# Distribution_Amp.net
KiCad netlist of a schematic drawn in Altium Designer
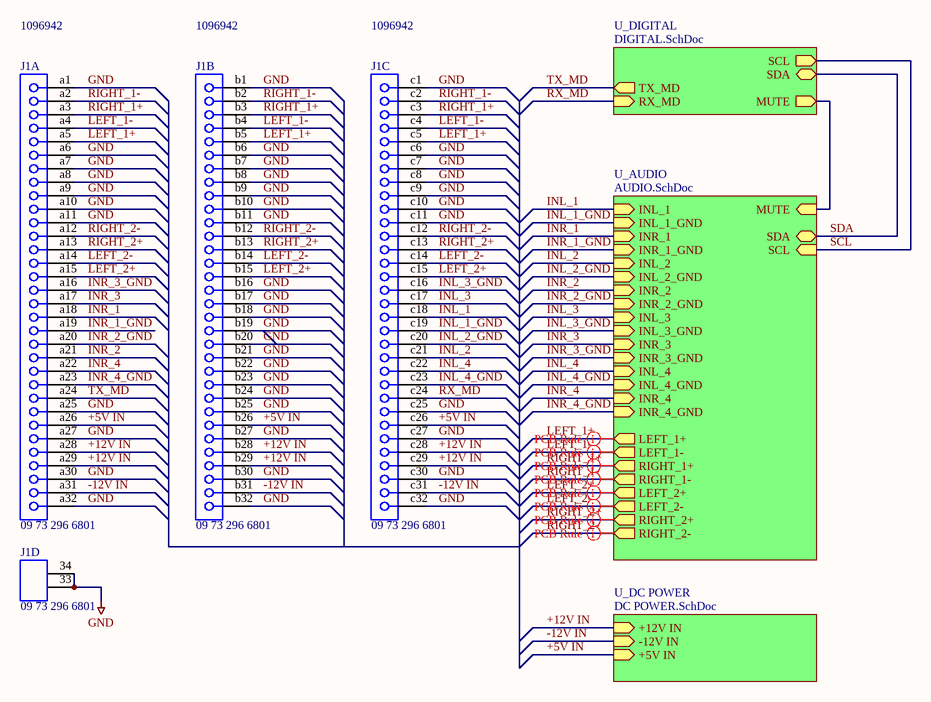
[diagram p0: Distribution Amp.SchDoc]

(export (version "E")
  (design (tool "Eeschema 10.0.6"))
  (components
    (comp (ref "J1")
      (value "09 73 296 6801")
      (footprint "0973296X801")
      (fields
        (field (name "MANUFACTURER") "HARTING")
        (field (name "MANUFACTURER PART NO.") "09732966801")
        (field (name "MOUSER PART NO.") "617-09-73-296-6801")
        (field (name "SUPPLIER PART NUMBER 3") "1096942")
      )
      (libsource (lib "HARTING DIN 41612 Type R") (part "09 73 296 6801"))
    )
  )
  (nets
    (net (code "1") (name "/+5V IN") (class "Default")
      (node (ref "J1") (pin "a26") (pinfunction "a26_a26") (pintype "passive"))
      (node (ref "J1") (pin "b26") (pinfunction "b26_b26") (pintype "passive"))
      (node (ref "J1") (pin "c26") (pinfunction "c26_c26") (pintype "passive"))
    )
    (net (code "2") (name "/+12V IN") (class "Default")
      (node (ref "J1") (pin "a28") (pinfunction "a28_a28") (pintype "passive"))
      (node (ref "J1") (pin "a29") (pinfunction "a29_a29") (pintype "passive"))
      (node (ref "J1") (pin "b28") (pinfunction "b28_b28") (pintype "passive"))
      (node (ref "J1") (pin "b29") (pinfunction "b29_b29") (pintype "passive"))
      (node (ref "J1") (pin "c28") (pinfunction "c28_c28") (pintype "passive"))
      (node (ref "J1") (pin "c29") (pinfunction "c29_c29") (pintype "passive"))
    )
    (net (code "3") (name "/-12V IN") (class "Default")
      (node (ref "J1") (pin "a31") (pinfunction "a31_a31") (pintype "passive"))
      (node (ref "J1") (pin "b31") (pinfunction "b31_b31") (pintype "passive"))
      (node (ref "J1") (pin "c31") (pinfunction "c31_c31") (pintype "passive"))
    )
    (net (code "4") (name "/INL_1") (class "Default")
      (node (ref "J1") (pin "c18") (pinfunction "c18_c18") (pintype "passive"))
    )
    (net (code "5") (name "/INL_1_GND") (class "Default")
      (node (ref "J1") (pin "c19") (pinfunction "c19_c19") (pintype "passive"))
    )
    (net (code "6") (name "/INL_2") (class "Default")
      (node (ref "J1") (pin "c21") (pinfunction "c21_c21") (pintype "passive"))
    )
    (net (code "7") (name "/INL_2_GND") (class "Default")
      (node (ref "J1") (pin "c20") (pinfunction "c20_c20") (pintype "passive"))
    )
    (net (code "8") (name "/INL_3") (class "Default")
      (node (ref "J1") (pin "c17") (pinfunction "c17_c17") (pintype "passive"))
    )
    (net (code "9") (name "/INL_3_GND") (class "Default")
      (node (ref "J1") (pin "c16") (pinfunction "c16_c16") (pintype "passive"))
    )
    (net (code "10") (name "/INL_4") (class "Default")
      (node (ref "J1") (pin "c22") (pinfunction "c22_c22") (pintype "passive"))
    )
    (net (code "11") (name "/INL_4_GND") (class "Default")
      (node (ref "J1") (pin "c23") (pinfunction "c23_c23") (pintype "passive"))
    )
    (net (code "12") (name "/INR_1") (class "Default")
      (node (ref "J1") (pin "a18") (pinfunction "a18_a18") (pintype "passive"))
    )
    (net (code "13") (name "/INR_1_GND") (class "Default")
      (node (ref "J1") (pin "a19") (pinfunction "a19_a19") (pintype "passive"))
    )
    (net (code "14") (name "/INR_2") (class "Default")
      (node (ref "J1") (pin "a21") (pinfunction "a21_a21") (pintype "passive"))
    )
    (net (code "15") (name "/INR_2_GND") (class "Default")
      (node (ref "J1") (pin "a20") (pinfunction "a20_a20") (pintype "passive"))
    )
    (net (code "16") (name "/INR_3") (class "Default")
      (node (ref "J1") (pin "a17") (pinfunction "a17_a17") (pintype "passive"))
    )
    (net (code "17") (name "/INR_3_GND") (class "Default")
      (node (ref "J1") (pin "a16") (pinfunction "a16_a16") (pintype "passive"))
    )
    (net (code "18") (name "/INR_4") (class "Default")
      (node (ref "J1") (pin "a22") (pinfunction "a22_a22") (pintype "passive"))
    )
    (net (code "19") (name "/INR_4_GND") (class "Default")
      (node (ref "J1") (pin "a23") (pinfunction "a23_a23") (pintype "passive"))
    )
    (net (code "20") (name "/LEFT_1+") (class "Default")
      (node (ref "J1") (pin "a5") (pinfunction "a5_a5") (pintype "passive"))
      (node (ref "J1") (pin "b5") (pinfunction "b5_b5") (pintype "passive"))
      (node (ref "J1") (pin "c5") (pinfunction "c5_c5") (pintype "passive"))
    )
    (net (code "21") (name "/LEFT_1-") (class "Default")
      (node (ref "J1") (pin "a4") (pinfunction "a4_a4") (pintype "passive"))
      (node (ref "J1") (pin "b4") (pinfunction "b4_b4") (pintype "passive"))
      (node (ref "J1") (pin "c4") (pinfunction "c4_c4") (pintype "passive"))
    )
    (net (code "22") (name "/LEFT_2+") (class "Default")
      (node (ref "J1") (pin "a15") (pinfunction "a15_a15") (pintype "passive"))
      (node (ref "J1") (pin "b15") (pinfunction "b15_b15") (pintype "passive"))
      (node (ref "J1") (pin "c15") (pinfunction "c15_c15") (pintype "passive"))
    )
    (net (code "23") (name "/LEFT_2-") (class "Default")
      (node (ref "J1") (pin "a14") (pinfunction "a14_a14") (pintype "passive"))
      (node (ref "J1") (pin "b14") (pinfunction "b14_b14") (pintype "passive"))
      (node (ref "J1") (pin "c14") (pinfunction "c14_c14") (pintype "passive"))
    )
    (net (code "25") (name "/RIGHT_1+") (class "Default")
      (node (ref "J1") (pin "a3") (pinfunction "a3_a3") (pintype "passive"))
      (node (ref "J1") (pin "b3") (pinfunction "b3_b3") (pintype "passive"))
      (node (ref "J1") (pin "c3") (pinfunction "c3_c3") (pintype "passive"))
    )
    (net (code "26") (name "/RIGHT_1-") (class "Default")
      (node (ref "J1") (pin "a2") (pinfunction "a2_a2") (pintype "passive"))
      (node (ref "J1") (pin "b2") (pinfunction "b2_b2") (pintype "passive"))
      (node (ref "J1") (pin "c2") (pinfunction "c2_c2") (pintype "passive"))
    )
    (net (code "27") (name "/RIGHT_2+") (class "Default")
      (node (ref "J1") (pin "a13") (pinfunction "a13_a13") (pintype "passive"))
      (node (ref "J1") (pin "b13") (pinfunction "b13_b13") (pintype "passive"))
      (node (ref "J1") (pin "c13") (pinfunction "c13_c13") (pintype "passive"))
    )
    (net (code "28") (name "/RIGHT_2-") (class "Default")
      (node (ref "J1") (pin "a12") (pinfunction "a12_a12") (pintype "passive"))
      (node (ref "J1") (pin "b12") (pinfunction "b12_b12") (pintype "passive"))
      (node (ref "J1") (pin "c12") (pinfunction "c12_c12") (pintype "passive"))
    )
    (net (code "29") (name "/RX_MD") (class "Default")
      (node (ref "J1") (pin "c24") (pinfunction "c24_c24") (pintype "passive"))
    )
    (net (code "32") (name "/TX_MD") (class "Default")
      (node (ref "J1") (pin "a24") (pinfunction "a24_a24") (pintype "passive"))
    )
    (net (code "33") (name "GND") (class "Default")
      (node (ref "J1") (pin "33") (pinfunction "MH1_33") (pintype "passive"))
      (node (ref "J1") (pin "34") (pinfunction "MH2_34") (pintype "passive"))
      (node (ref "J1") (pin "a1") (pinfunction "a1_a1") (pintype "passive"))
      (node (ref "J1") (pin "a10") (pinfunction "a10_a10") (pintype "passive"))
      (node (ref "J1") (pin "a11") (pinfunction "a11_a11") (pintype "passive"))
      (node (ref "J1") (pin "a25") (pinfunction "a25_a25") (pintype "passive"))
      (node (ref "J1") (pin "a27") (pinfunction "a27_a27") (pintype "passive"))
      (node (ref "J1") (pin "a30") (pinfunction "a30_a30") (pintype "passive"))
      (node (ref "J1") (pin "a32") (pinfunction "a32_a32") (pintype "passive"))
      (node (ref "J1") (pin "a6") (pinfunction "a6_a6") (pintype "passive"))
      (node (ref "J1") (pin "a7") (pinfunction "a7_a7") (pintype "passive"))
      (node (ref "J1") (pin "a8") (pinfunction "a8_a8") (pintype "passive"))
      (node (ref "J1") (pin "a9") (pinfunction "a9_a9") (pintype "passive"))
      (node (ref "J1") (pin "b1") (pinfunction "b1_b1") (pintype "passive"))
      (node (ref "J1") (pin "b10") (pinfunction "b10_b10") (pintype "passive"))
      (node (ref "J1") (pin "b11") (pinfunction "b11_b11") (pintype "passive"))
      (node (ref "J1") (pin "b16") (pinfunction "b16_b16") (pintype "passive"))
      (node (ref "J1") (pin "b17") (pinfunction "b17_b17") (pintype "passive"))
      (node (ref "J1") (pin "b18") (pinfunction "b18_b18") (pintype "passive"))
      (node (ref "J1") (pin "b19") (pinfunction "b19_b19") (pintype "passive"))
      (node (ref "J1") (pin "b20") (pinfunction "b20_b20") (pintype "passive"))
      (node (ref "J1") (pin "b21") (pinfunction "b21_b21") (pintype "passive"))
      (node (ref "J1") (pin "b22") (pinfunction "b22_b22") (pintype "passive"))
      (node (ref "J1") (pin "b23") (pinfunction "b23_b23") (pintype "passive"))
      (node (ref "J1") (pin "b24") (pinfunction "b24_b24") (pintype "passive"))
      (node (ref "J1") (pin "b25") (pinfunction "b25_b25") (pintype "passive"))
      (node (ref "J1") (pin "b27") (pinfunction "b27_b27") (pintype "passive"))
      (node (ref "J1") (pin "b30") (pinfunction "b30_b30") (pintype "passive"))
      (node (ref "J1") (pin "b32") (pinfunction "b32_b32") (pintype "passive"))
      (node (ref "J1") (pin "b6") (pinfunction "b6_b6") (pintype "passive"))
      (node (ref "J1") (pin "b7") (pinfunction "b7_b7") (pintype "passive"))
      (node (ref "J1") (pin "b8") (pinfunction "b8_b8") (pintype "passive"))
      (node (ref "J1") (pin "b9") (pinfunction "b9_b9") (pintype "passive"))
      (node (ref "J1") (pin "c1") (pinfunction "c1_c1") (pintype "passive"))
      (node (ref "J1") (pin "c10") (pinfunction "c10_c10") (pintype "passive"))
      (node (ref "J1") (pin "c11") (pinfunction "c11_c11") (pintype "passive"))
      (node (ref "J1") (pin "c25") (pinfunction "c25_c25") (pintype "passive"))
      (node (ref "J1") (pin "c27") (pinfunction "c27_c27") (pintype "passive"))
      (node (ref "J1") (pin "c30") (pinfunction "c30_c30") (pintype "passive"))
      (node (ref "J1") (pin "c32") (pinfunction "c32_c32") (pintype "passive"))
      (node (ref "J1") (pin "c6") (pinfunction "c6_c6") (pintype "passive"))
      (node (ref "J1") (pin "c7") (pinfunction "c7_c7") (pintype "passive"))
      (node (ref "J1") (pin "c8") (pinfunction "c8_c8") (pintype "passive"))
      (node (ref "J1") (pin "c9") (pinfunction "c9_c9") (pintype "passive"))
    )
  )
)
